# SMA_Connector.net
KiCad netlist of a schematic drawn in Altium Designer
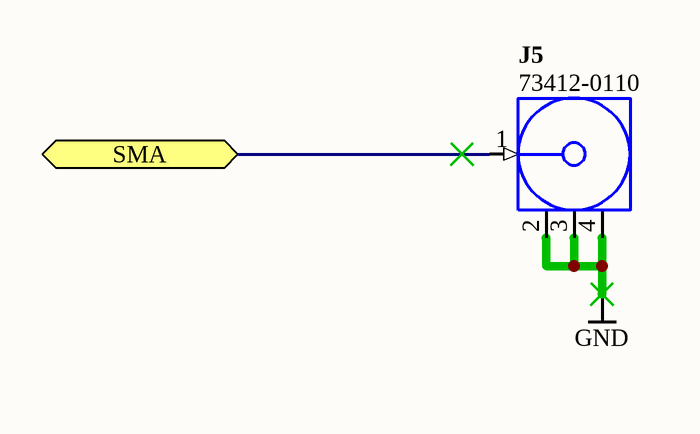
[diagram p0: SMA_Connector.SchDoc]

(export (version "E")
  (design (tool "Eeschema 10.0.6"))
  (components
    (comp (ref "J5")
      (value "73412-0110")
      (footprint "MOLX-73412-0110")
      (description "Microcoaxial RF, 50 Ohm, PCB Vertical Jack Receptacle, SMT, 1.25mm Mounted Height")
      (libsource (lib "Altium Vault") (part "CMP-5222-00000-1"))
    )
  )
  (nets
    (net (code "1") (name "/SMA") (class "Default")
      (node (ref "J5") (pin "1") (pinfunction "Signal_1") (pintype "input"))
    )
    (net (code "2") (name "GND") (class "Default")
      (node (ref "J5") (pin "2") (pinfunction "GND_2") (pintype "power_in"))
      (node (ref "J5") (pin "3") (pinfunction "GND_3") (pintype "power_in"))
      (node (ref "J5") (pin "4") (pinfunction "GND_4") (pintype "power_in"))
    )
  )
)
